# Sheet1.net
KiCad netlist of a schematic drawn in Altium Designer
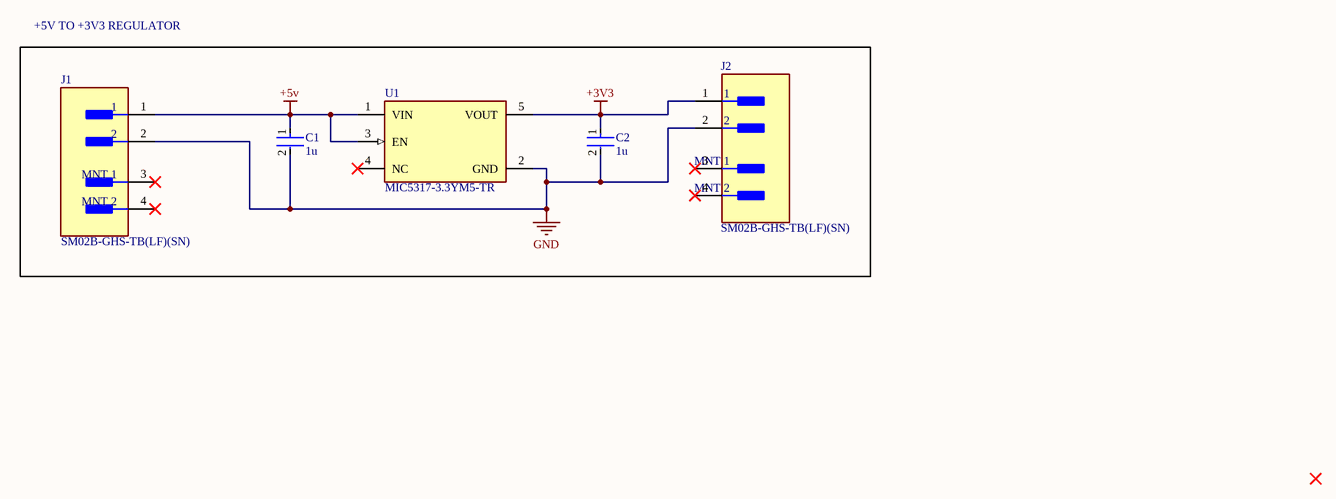
[diagram p0: Sheet1.SchDoc]

(export (version "E")
  (design (tool "Eeschema 10.0.6"))
  (components
    (comp (ref "C1")
      (value "1u")
      (footprint "FP-0805-L_2_01_0_2-W_1_25-MFG")
      (description "General Purpose Ceramic Capacitor, 0805, 1uF, 10%, X7R, 15%, 10V")
      (fields (field (name "TOLERANCE") "10%") (field (name "VOLTAGE") "10V"))
      (libsource (lib "Altium Content Vault") (part "b4654b650e69147ec39a6b967a45e02"))
    )
    (comp (ref "C2")
      (value "1u")
      (footprint "FP-0805-L_2_01_0_2-W_1_25-MFG")
      (description "General Purpose Ceramic Capacitor, 0805, 1uF, 10%, X7R, 15%, 10V")
      (fields (field (name "TOLERANCE") "10%") (field (name "VOLTAGE") "10V"))
      (libsource (lib "Altium Content Vault") (part "b4654b650e69147ec39a6b967a45e02"))
    )
    (comp (ref "J1")
      (value "SM02B-GHS-TB(LF)(SN)")
      (footprint "FP-SM02B-GHS-TB_LF_SN-MFG")
      (description "CONN HEADER SMD R/A 2POS 1.25MM")
      (libsource (lib "") (part "56ec3178a87b3978bdc1b3682cd516a_1"))
    )
    (comp (ref "J2")
      (value "SM02B-GHS-TB(LF)(SN)")
      (footprint "FP-SM02B-GHS-TB_LF_SN-MFG")
      (description "CONN HEADER SMD R/A 2POS 1.25MM")
      (libsource (lib "Altium Content Vault") (part "56ec3178a87b3978bdc1b3682cd516a"))
    )
    (comp (ref "U1")
      (value "MIC5317-3.3YM5-TR")
      (footprint "FP-SOT23-5LD-PL-1-MFG")
      (description "IC REG LINEAR 3.3V 150MA SOT23-5")
      (libsource (lib "Altium Content Vault") (part "0a093dae7315cdc977fd108dde87457"))
    )
  )
  (nets
    (net (code "1") (name "+3V3") (class "Default")
      (node (ref "C2") (pin "1") (pinfunction "1_1") (pintype "passive"))
      (node (ref "J2") (pin "1") (pinfunction "1_1") (pintype "passive"))
      (node (ref "U1") (pin "5") (pinfunction "VOUT_5") (pintype "power_in"))
    )
    (net (code "2") (name "+5v") (class "Default")
      (node (ref "C1") (pin "1") (pinfunction "1_1") (pintype "passive"))
      (node (ref "J1") (pin "1") (pinfunction "1_1") (pintype "passive"))
      (node (ref "U1") (pin "1") (pinfunction "VIN_1") (pintype "power_in"))
      (node (ref "U1") (pin "3") (pinfunction "EN_3") (pintype "input"))
    )
    (net (code "3") (name "GND") (class "Default")
      (node (ref "C1") (pin "2") (pinfunction "2_2") (pintype "passive"))
      (node (ref "C2") (pin "2") (pinfunction "2_2") (pintype "passive"))
      (node (ref "J1") (pin "2") (pinfunction "2_2") (pintype "passive"))
      (node (ref "J2") (pin "2") (pinfunction "2_2") (pintype "passive"))
      (node (ref "U1") (pin "2") (pinfunction "GND_2") (pintype "power_in"))
    )
    (net (code "4") (name "unconnected-(J1-MNT_1-Pad3)") (class "Default")
      (node (ref "J1") (pin "3") (pinfunction "MNT_1_3") (pintype "passive+no_connect"))
    )
    (net (code "5") (name "unconnected-(J1-MNT_2-Pad4)") (class "Default")
      (node (ref "J1") (pin "4") (pinfunction "MNT_2_4") (pintype "passive+no_connect"))
    )
    (net (code "6") (name "unconnected-(J2-MNT_1-Pad3)") (class "Default")
      (node (ref "J2") (pin "3") (pinfunction "MNT_1_3") (pintype "passive+no_connect"))
    )
    (net (code "7") (name "unconnected-(J2-MNT_2-Pad4)") (class "Default")
      (node (ref "J2") (pin "4") (pinfunction "MNT_2_4") (pintype "passive+no_connect"))
    )
    (net (code "8") (name "unconnected-(U1-NC-Pad4)") (class "Default")
      (node (ref "U1") (pin "4") (pinfunction "NC_4") (pintype "passive+no_connect"))
    )
  )
)
